# aw_801_oscilloscope.net
KiCad netlist of a schematic drawn in EAGLE
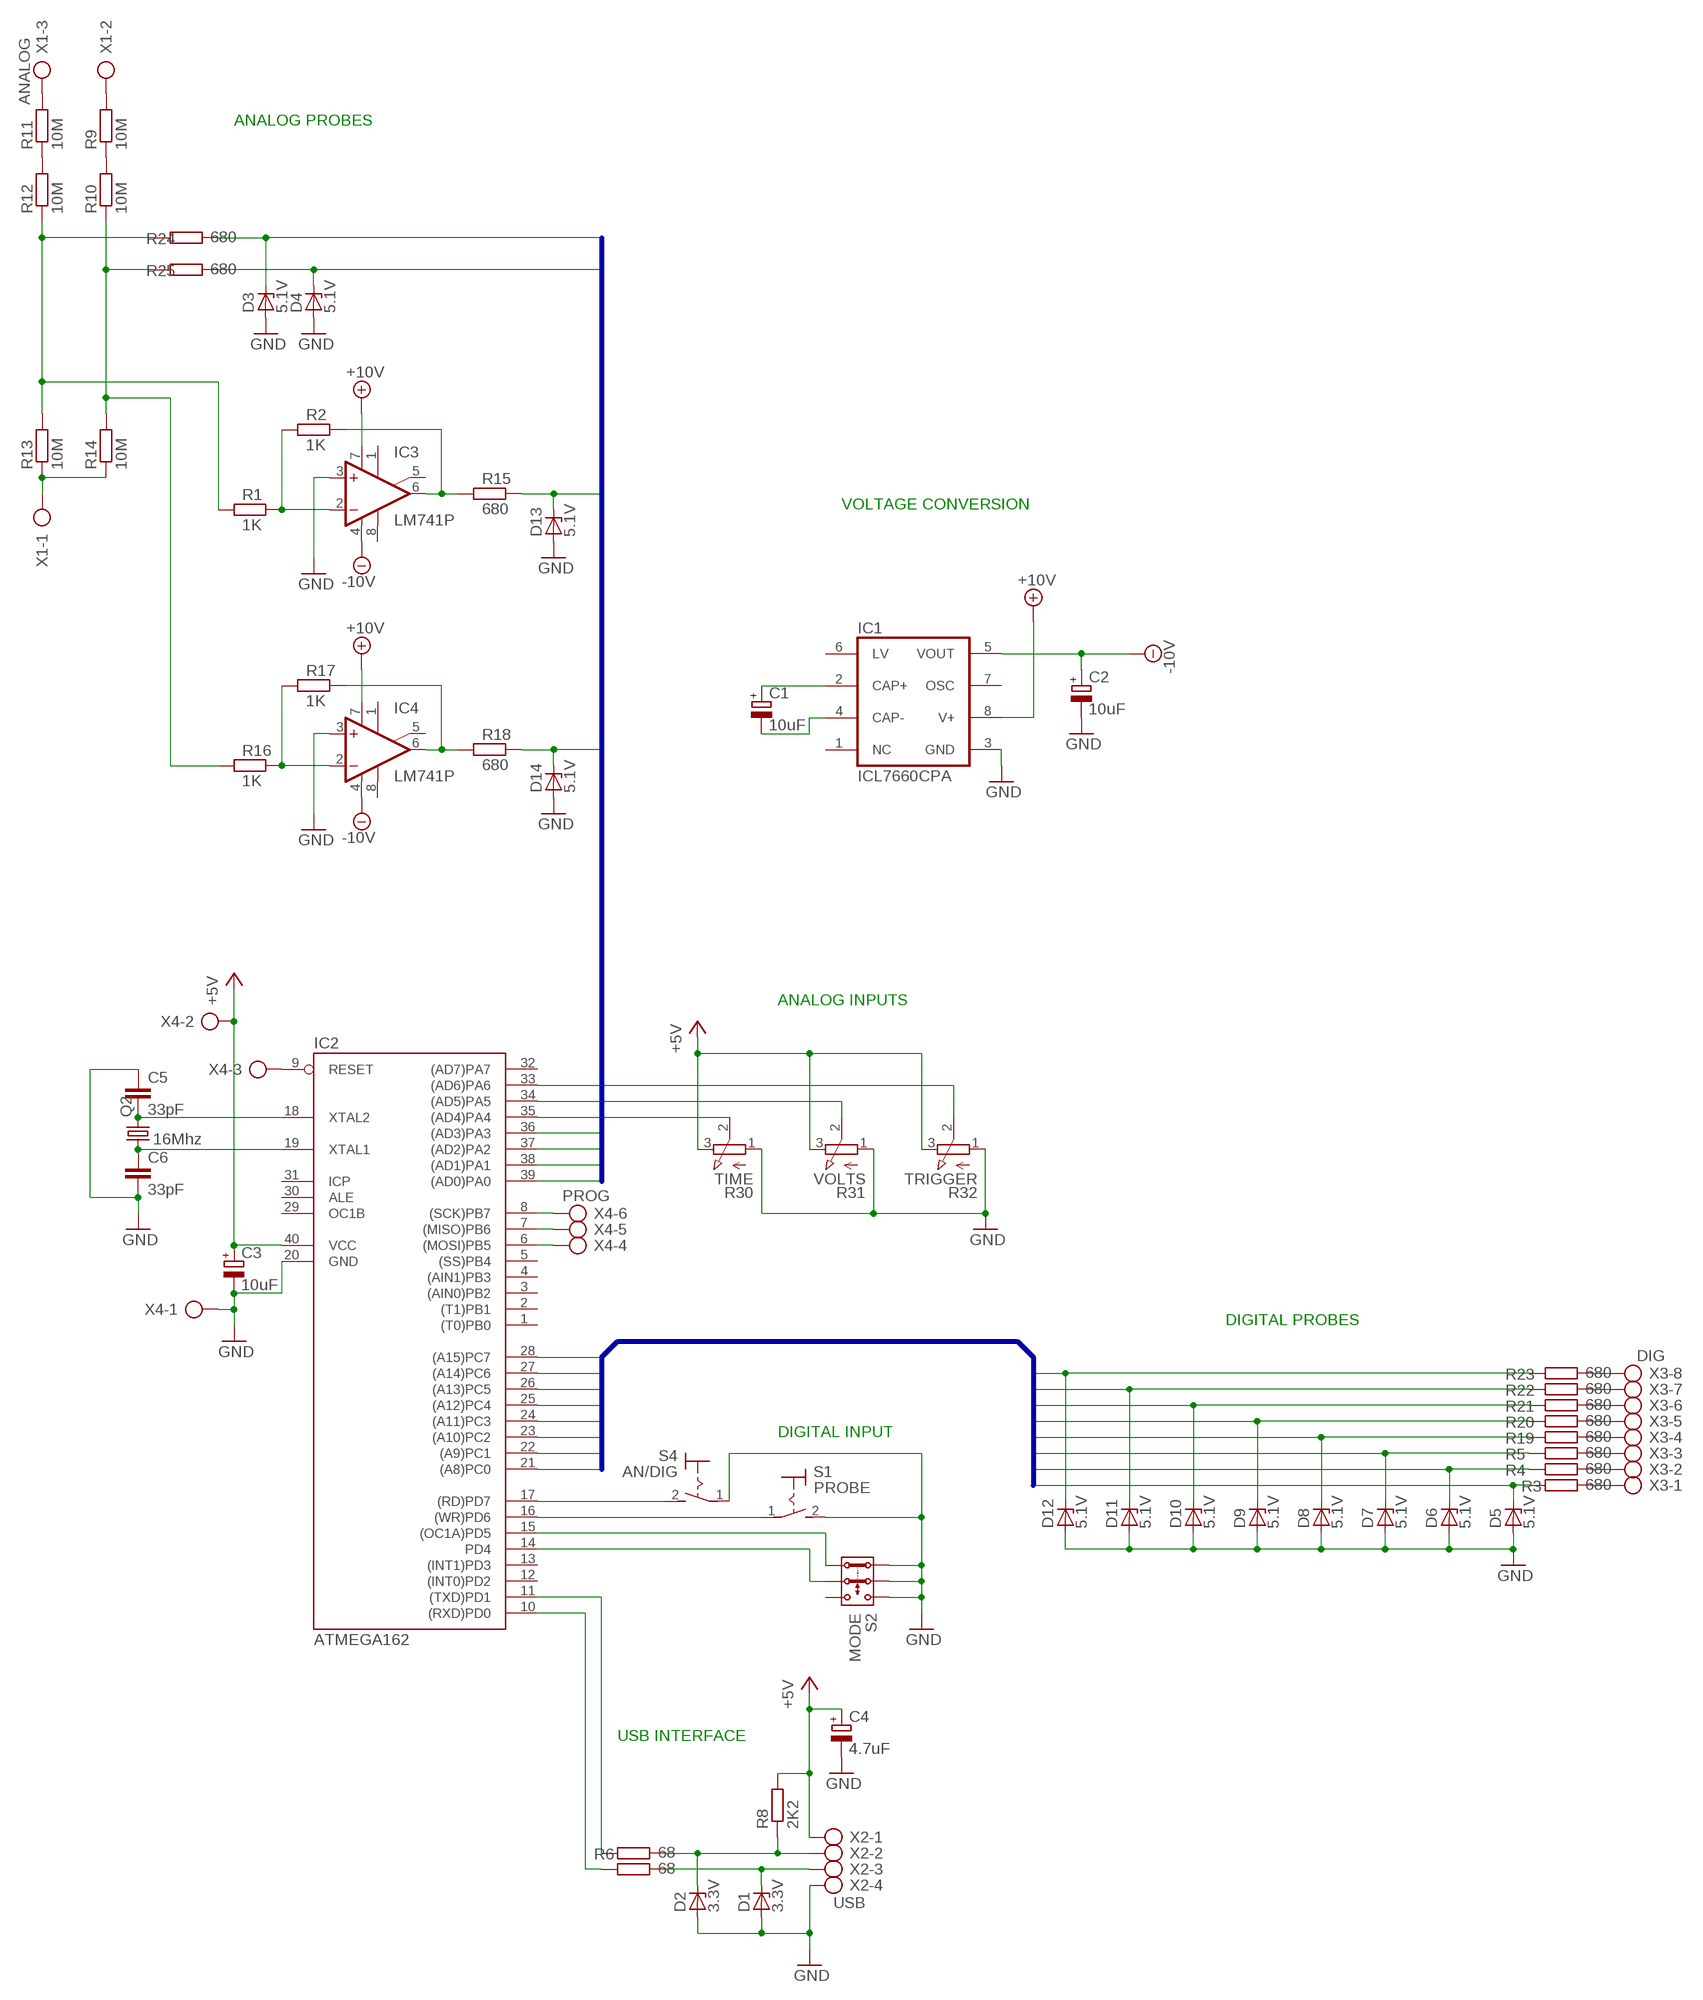
[diagram p0: schematic, sheet 1]

(export (version "E")
  (design (tool "Eeschema 10.0.6"))
  (components
    (comp (ref "C1")
      (value "10uF")
      (footprint "eagle-import:E2,5-6")
      (libsource (lib "eagle-import") (part "CPOL-EUE2.5-6"))
    )
    (comp (ref "C2")
      (value "10uF")
      (footprint "eagle-import:E2,5-6")
      (libsource (lib "eagle-import") (part "CPOL-EUE2.5-6"))
    )
    (comp (ref "C3")
      (value "10uF")
      (footprint "eagle-import:E2,5-6")
      (libsource (lib "eagle-import") (part "CPOL-EUE2.5-6"))
    )
    (comp (ref "C4")
      (value "4.7uF")
      (footprint "eagle-import:E2,5-6")
      (libsource (lib "eagle-import") (part "CPOL-EUE2.5-6"))
    )
    (comp (ref "C5")
      (value "33pF")
      (footprint "eagle-import:C050-030X075")
      (libsource (lib "eagle-import") (part "C-EU050-030X075"))
    )
    (comp (ref "C6")
      (value "33pF")
      (footprint "eagle-import:C050-030X075")
      (libsource (lib "eagle-import") (part "C-EU050-030X075"))
    )
    (comp (ref "D1")
      (value "3.3V")
      (footprint "eagle-import:DO35Z10")
      (libsource (lib "eagle-import") (part "ZENER-DIODEDO35Z10"))
    )
    (comp (ref "D2")
      (value "3.3V")
      (footprint "eagle-import:DO35Z10")
      (libsource (lib "eagle-import") (part "ZENER-DIODEDO35Z10"))
    )
    (comp (ref "D3")
      (value "5.1V")
      (footprint "eagle-import:DO35Z10")
      (libsource (lib "eagle-import") (part "ZENER-DIODEDO35Z10"))
    )
    (comp (ref "D4")
      (value "5.1V")
      (footprint "eagle-import:DO35Z10")
      (libsource (lib "eagle-import") (part "ZENER-DIODEDO35Z10"))
    )
    (comp (ref "D5")
      (value "5.1V")
      (footprint "eagle-import:DO35Z10")
      (libsource (lib "eagle-import") (part "ZENER-DIODEDO35Z10"))
    )
    (comp (ref "D6")
      (value "5.1V")
      (footprint "eagle-import:DO35Z10")
      (libsource (lib "eagle-import") (part "ZENER-DIODEDO35Z10"))
    )
    (comp (ref "D7")
      (value "5.1V")
      (footprint "eagle-import:DO35Z10")
      (libsource (lib "eagle-import") (part "ZENER-DIODEDO35Z10"))
    )
    (comp (ref "D8")
      (value "5.1V")
      (footprint "eagle-import:DO35Z10")
      (libsource (lib "eagle-import") (part "ZENER-DIODEDO35Z10"))
    )
    (comp (ref "D9")
      (value "5.1V")
      (footprint "eagle-import:DO35Z10")
      (libsource (lib "eagle-import") (part "ZENER-DIODEDO35Z10"))
    )
    (comp (ref "D10")
      (value "5.1V")
      (footprint "eagle-import:DO35Z10")
      (libsource (lib "eagle-import") (part "ZENER-DIODEDO35Z10"))
    )
    (comp (ref "D11")
      (value "5.1V")
      (footprint "eagle-import:DO35Z10")
      (libsource (lib "eagle-import") (part "ZENER-DIODEDO35Z10"))
    )
    (comp (ref "D12")
      (value "5.1V")
      (footprint "eagle-import:DO35Z10")
      (libsource (lib "eagle-import") (part "ZENER-DIODEDO35Z10"))
    )
    (comp (ref "D13")
      (value "5.1V")
      (footprint "eagle-import:DO35Z10")
      (libsource (lib "eagle-import") (part "ZENER-DIODEDO35Z10"))
    )
    (comp (ref "D14")
      (value "5.1V")
      (footprint "eagle-import:DO35Z10")
      (libsource (lib "eagle-import") (part "ZENER-DIODEDO35Z10"))
    )
    (comp (ref "IC1")
      (value "ICL7660CPA")
      (footprint "eagle-import:DIL08")
      (fields (field (name "MF") "INTERSIL"))
      (libsource (lib "eagle-import") (part "ICL7660CPA"))
    )
    (comp (ref "IC2")
      (value "ATMEGA162")
      (footprint "eagle-import:DIL40")
      (libsource (lib "eagle-import") (part "AT90S8515P"))
    )
    (comp (ref "IC3")
      (value "LM741P")
      (footprint "eagle-import:DIL08")
      (libsource (lib "eagle-import") (part "741PLM"))
    )
    (comp (ref "IC4")
      (value "LM741P")
      (footprint "eagle-import:DIL08")
      (libsource (lib "eagle-import") (part "741PLM"))
    )
    (comp (ref "Q2")
      (value "16Mhz")
      (footprint "eagle-import:HC49U70")
      (libsource (lib "eagle-import") (part "CRYSTALHC49U70"))
    )
    (comp (ref "R1")
      (value "1K")
      (footprint "eagle-import:0207_10")
      (libsource (lib "eagle-import") (part "R-EU_0207/10"))
    )
    (comp (ref "R2")
      (value "1K")
      (footprint "eagle-import:0207_10")
      (libsource (lib "eagle-import") (part "R-EU_0207/10"))
    )
    (comp (ref "R3")
      (value "680")
      (footprint "eagle-import:0207_10")
      (libsource (lib "eagle-import") (part "R-EU_0207/10"))
    )
    (comp (ref "R4")
      (value "680")
      (footprint "eagle-import:0207_10")
      (libsource (lib "eagle-import") (part "R-EU_0207/10"))
    )
    (comp (ref "R5")
      (value "680")
      (footprint "eagle-import:0207_10")
      (libsource (lib "eagle-import") (part "R-EU_0207/10"))
    )
    (comp (ref "R6")
      (value "68")
      (footprint "eagle-import:0207_10")
      (libsource (lib "eagle-import") (part "R-EU_0207/10"))
    )
    (comp (ref "R7")
      (value "68")
      (footprint "eagle-import:0207_10")
      (libsource (lib "eagle-import") (part "R-EU_0207/10"))
    )
    (comp (ref "R8")
      (value "2K2")
      (footprint "eagle-import:0207_10")
      (libsource (lib "eagle-import") (part "R-EU_0207/10"))
    )
    (comp (ref "R9")
      (value "10M")
      (footprint "eagle-import:0207_10")
      (libsource (lib "eagle-import") (part "R-EU_0207/10"))
    )
    (comp (ref "R10")
      (value "10M")
      (footprint "eagle-import:0207_10")
      (libsource (lib "eagle-import") (part "R-EU_0207/10"))
    )
    (comp (ref "R11")
      (value "10M")
      (footprint "eagle-import:0207_10")
      (libsource (lib "eagle-import") (part "R-EU_0207/10"))
    )
    (comp (ref "R12")
      (value "10M")
      (footprint "eagle-import:0207_10")
      (libsource (lib "eagle-import") (part "R-EU_0207/10"))
    )
    (comp (ref "R13")
      (value "10M")
      (footprint "eagle-import:0207_10")
      (libsource (lib "eagle-import") (part "R-EU_0207/10"))
    )
    (comp (ref "R14")
      (value "10M")
      (footprint "eagle-import:0207_10")
      (libsource (lib "eagle-import") (part "R-EU_0207/10"))
    )
    (comp (ref "R15")
      (value "680")
      (footprint "eagle-import:0207_10")
      (libsource (lib "eagle-import") (part "R-EU_0207/10"))
    )
    (comp (ref "R16")
      (value "1K")
      (footprint "eagle-import:0207_10")
      (libsource (lib "eagle-import") (part "R-EU_0207/10"))
    )
    (comp (ref "R17")
      (value "1K")
      (footprint "eagle-import:0207_10")
      (libsource (lib "eagle-import") (part "R-EU_0207/10"))
    )
    (comp (ref "R18")
      (value "680")
      (footprint "eagle-import:0207_10")
      (libsource (lib "eagle-import") (part "R-EU_0207/10"))
    )
    (comp (ref "R19")
      (value "680")
      (footprint "eagle-import:0207_10")
      (libsource (lib "eagle-import") (part "R-EU_0207/10"))
    )
    (comp (ref "R20")
      (value "680")
      (footprint "eagle-import:0207_10")
      (libsource (lib "eagle-import") (part "R-EU_0207/10"))
    )
    (comp (ref "R21")
      (value "680")
      (footprint "eagle-import:0207_10")
      (libsource (lib "eagle-import") (part "R-EU_0207/10"))
    )
    (comp (ref "R22")
      (value "680")
      (footprint "eagle-import:0207_10")
      (libsource (lib "eagle-import") (part "R-EU_0207/10"))
    )
    (comp (ref "R23")
      (value "680")
      (footprint "eagle-import:0207_10")
      (libsource (lib "eagle-import") (part "R-EU_0207/10"))
    )
    (comp (ref "R24")
      (value "680")
      (footprint "eagle-import:0207_10")
      (libsource (lib "eagle-import") (part "R-EU_0207/10"))
    )
    (comp (ref "R25")
      (value "680")
      (footprint "eagle-import:0207_10")
      (libsource (lib "eagle-import") (part "R-EU_0207/10"))
    )
    (comp (ref "R30")
      (value "TIME")
      (footprint "eagle-import:3RP_1610N")
      (libsource (lib "eagle-import") (part "3RP/1610N"))
    )
    (comp (ref "R31")
      (value "VOLTS")
      (footprint "eagle-import:3RP_1610N")
      (libsource (lib "eagle-import") (part "3RP/1610N"))
    )
    (comp (ref "R32")
      (value "TRIGGER")
      (footprint "eagle-import:3RP_1610N")
      (libsource (lib "eagle-import") (part "3RP/1610N"))
    )
    (comp (ref "S1")
      (value "PROBE")
      (footprint "eagle-import:MS243")
      (libsource (lib "eagle-import") (part "MS243"))
    )
    (comp (ref "S2")
      (value "MODE")
      (footprint "eagle-import:2P2T")
      (libsource (lib "eagle-import") (part "2P2T"))
    )
    (comp (ref "S4")
      (value "AN/DIG")
      (footprint "eagle-import:MS243")
      (libsource (lib "eagle-import") (part "MS243"))
    )
    (comp (ref "X1")
      (value "ANALOG")
      (footprint "eagle-import:AK500_3")
      (libsource (lib "eagle-import") (part "AK500/3"))
    )
    (comp (ref "X2")
      (value "USB")
      (footprint "eagle-import:AK500_4")
      (libsource (lib "eagle-import") (part "AK500/4"))
    )
    (comp (ref "X3")
      (value "DIG")
      (footprint "eagle-import:AK500_8")
      (libsource (lib "eagle-import") (part "AK500/8"))
    )
    (comp (ref "X4")
      (value "PROG")
      (footprint "eagle-import:AK300_6")
      (libsource (lib "eagle-import") (part "AK300/6"))
    )
  )
  (nets
    (net (code "1") (name "+5V") (class "Default")
      (node (ref "C3") (pin "+") (pinfunction "+_+") (pintype "passive"))
      (node (ref "C4") (pin "+") (pinfunction "+_+") (pintype "passive"))
      (node (ref "IC2") (pin "40") (pinfunction "VCC_40") (pintype "power_in"))
      (node (ref "R30") (pin "3") (pinfunction "E_3") (pintype "passive"))
      (node (ref "R31") (pin "3") (pinfunction "E_3") (pintype "passive"))
      (node (ref "R32") (pin "3") (pinfunction "E_3") (pintype "passive"))
      (node (ref "R8") (pin "2") (pinfunction "2_2") (pintype "passive"))
      (node (ref "X2") (pin "1") (pinfunction "KL_1") (pintype "passive"))
      (node (ref "X4") (pin "2") (pinfunction "KL_2") (pintype "passive"))
    )
    (net (code "2") (name "+10V") (class "Default")
      (node (ref "IC1") (pin "8") (pinfunction "V+_8") (pintype "power_in"))
      (node (ref "IC3") (pin "7") (pinfunction "V+_7") (pintype "power_in"))
      (node (ref "IC4") (pin "7") (pinfunction "V+_7") (pintype "power_in"))
    )
    (net (code "3") (name "-10V") (class "Default")
      (node (ref "C2") (pin "+") (pinfunction "+_+") (pintype "passive"))
      (node (ref "IC1") (pin "5") (pinfunction "VOUT_5") (pintype "power_in"))
      (node (ref "IC3") (pin "4") (pinfunction "V-_4") (pintype "power_in"))
      (node (ref "IC4") (pin "4") (pinfunction "V-_4") (pintype "power_in"))
    )
    (net (code "4") (name "/ANALOG0") (class "Default")
      (node (ref "D3") (pin "C") (pinfunction "C_C") (pintype "passive"))
      (node (ref "IC2") (pin "39") (pinfunction "(AD0)PA0_39") (pintype "bidirectional"))
      (node (ref "R24") (pin "2") (pinfunction "2_2") (pintype "passive"))
    )
    (net (code "5") (name "/ANALOG1") (class "Default")
      (node (ref "D4") (pin "C") (pinfunction "C_C") (pintype "passive"))
      (node (ref "IC2") (pin "38") (pinfunction "(AD1)PA1_38") (pintype "bidirectional"))
      (node (ref "R25") (pin "2") (pinfunction "2_2") (pintype "passive"))
    )
    (net (code "6") (name "/ANALOG2") (class "Default")
      (node (ref "D13") (pin "C") (pinfunction "C_C") (pintype "passive"))
      (node (ref "IC2") (pin "37") (pinfunction "(AD2)PA2_37") (pintype "bidirectional"))
      (node (ref "R15") (pin "2") (pinfunction "2_2") (pintype "passive"))
    )
    (net (code "7") (name "/ANALOG3") (class "Default")
      (node (ref "D14") (pin "C") (pinfunction "C_C") (pintype "passive"))
      (node (ref "IC2") (pin "36") (pinfunction "(AD3)PA3_36") (pintype "bidirectional"))
      (node (ref "R18") (pin "2") (pinfunction "2_2") (pintype "passive"))
    )
    (net (code "8") (name "/DIG0") (class "Default")
      (node (ref "D12") (pin "C") (pinfunction "C_C") (pintype "passive"))
      (node (ref "IC2") (pin "21") (pinfunction "(A8)PC0_21") (pintype "bidirectional"))
      (node (ref "R23") (pin "1") (pinfunction "1_1") (pintype "passive"))
    )
    (net (code "9") (name "/DIG1") (class "Default")
      (node (ref "D11") (pin "C") (pinfunction "C_C") (pintype "passive"))
      (node (ref "IC2") (pin "22") (pinfunction "(A9)PC1_22") (pintype "bidirectional"))
      (node (ref "R22") (pin "1") (pinfunction "1_1") (pintype "passive"))
    )
    (net (code "10") (name "/DIG2") (class "Default")
      (node (ref "D10") (pin "C") (pinfunction "C_C") (pintype "passive"))
      (node (ref "IC2") (pin "23") (pinfunction "(A10)PC2_23") (pintype "bidirectional"))
      (node (ref "R21") (pin "1") (pinfunction "1_1") (pintype "passive"))
    )
    (net (code "11") (name "/DIG3") (class "Default")
      (node (ref "D9") (pin "C") (pinfunction "C_C") (pintype "passive"))
      (node (ref "IC2") (pin "24") (pinfunction "(A11)PC3_24") (pintype "bidirectional"))
      (node (ref "R20") (pin "1") (pinfunction "1_1") (pintype "passive"))
    )
    (net (code "12") (name "/DIG4") (class "Default")
      (node (ref "D8") (pin "C") (pinfunction "C_C") (pintype "passive"))
      (node (ref "IC2") (pin "25") (pinfunction "(A12)PC4_25") (pintype "bidirectional"))
      (node (ref "R19") (pin "1") (pinfunction "1_1") (pintype "passive"))
    )
    (net (code "13") (name "/DIG5") (class "Default")
      (node (ref "D7") (pin "C") (pinfunction "C_C") (pintype "passive"))
      (node (ref "IC2") (pin "26") (pinfunction "(A13)PC5_26") (pintype "bidirectional"))
      (node (ref "R5") (pin "1") (pinfunction "1_1") (pintype "passive"))
    )
    (net (code "14") (name "/DIG6") (class "Default")
      (node (ref "D6") (pin "C") (pinfunction "C_C") (pintype "passive"))
      (node (ref "IC2") (pin "27") (pinfunction "(A14)PC6_27") (pintype "bidirectional"))
      (node (ref "R4") (pin "1") (pinfunction "1_1") (pintype "passive"))
    )
    (net (code "15") (name "/DIG7") (class "Default")
      (node (ref "D5") (pin "C") (pinfunction "C_C") (pintype "passive"))
      (node (ref "IC2") (pin "28") (pinfunction "(A15)PC7_28") (pintype "bidirectional"))
      (node (ref "R3") (pin "1") (pinfunction "1_1") (pintype "passive"))
    )
    (net (code "16") (name "GND") (class "Default")
      (node (ref "C2") (pin "-") (pinfunction "-_-") (pintype "passive"))
      (node (ref "C3") (pin "-") (pinfunction "-_-") (pintype "passive"))
      (node (ref "C4") (pin "-") (pinfunction "-_-") (pintype "passive"))
      (node (ref "C5") (pin "1") (pinfunction "1_1") (pintype "passive"))
      (node (ref "C6") (pin "2") (pinfunction "2_2") (pintype "passive"))
      (node (ref "D1") (pin "A") (pinfunction "A_A") (pintype "passive"))
      (node (ref "D10") (pin "A") (pinfunction "A_A") (pintype "passive"))
      (node (ref "D11") (pin "A") (pinfunction "A_A") (pintype "passive"))
      (node (ref "D12") (pin "A") (pinfunction "A_A") (pintype "passive"))
      (node (ref "D13") (pin "A") (pinfunction "A_A") (pintype "passive"))
      (node (ref "D14") (pin "A") (pinfunction "A_A") (pintype "passive"))
      (node (ref "D2") (pin "A") (pinfunction "A_A") (pintype "passive"))
      (node (ref "D3") (pin "A") (pinfunction "A_A") (pintype "passive"))
      (node (ref "D4") (pin "A") (pinfunction "A_A") (pintype "passive"))
      (node (ref "D5") (pin "A") (pinfunction "A_A") (pintype "passive"))
      (node (ref "D6") (pin "A") (pinfunction "A_A") (pintype "passive"))
      (node (ref "D7") (pin "A") (pinfunction "A_A") (pintype "passive"))
      (node (ref "D8") (pin "A") (pinfunction "A_A") (pintype "passive"))
      (node (ref "D9") (pin "A") (pinfunction "A_A") (pintype "passive"))
      (node (ref "IC1") (pin "3") (pinfunction "GND_3") (pintype "power_in"))
      (node (ref "IC2") (pin "20") (pinfunction "GND_20") (pintype "power_in"))
      (node (ref "IC3") (pin "3") (pinfunction "+IN_3") (pintype "input"))
      (node (ref "IC4") (pin "3") (pinfunction "+IN_3") (pintype "input"))
      (node (ref "R30") (pin "1") (pinfunction "A_1") (pintype "passive"))
      (node (ref "R31") (pin "1") (pinfunction "A_1") (pintype "passive"))
      (node (ref "R32") (pin "1") (pinfunction "A_1") (pintype "passive"))
      (node (ref "S1") (pin "2") (pinfunction "S_2") (pintype "passive"))
      (node (ref "S2") (pin "1.1") (pinfunction "1.1_1.1") (pintype "passive"))
      (node (ref "S2") (pin "2.1") (pinfunction "2.1_2.1") (pintype "passive"))
      (node (ref "S2") (pin "3.1") (pinfunction "3.1_3.1") (pintype "passive"))
      (node (ref "S4") (pin "1") (pinfunction "P_1") (pintype "passive"))
      (node (ref "X2") (pin "4") (pinfunction "KL_4") (pintype "passive"))
      (node (ref "X4") (pin "1") (pinfunction "KL_1") (pintype "passive"))
    )
    (net (code "17") (name "Net-(IC1-CAP+)") (class "Default")
      (node (ref "C1") (pin "+") (pinfunction "+_+") (pintype "passive"))
      (node (ref "IC1") (pin "2") (pinfunction "CAP+_2") (pintype "passive"))
    )
    (net (code "18") (name "Net-(IC1-CAP-)") (class "Default")
      (node (ref "C1") (pin "-") (pinfunction "-_-") (pintype "passive"))
      (node (ref "IC1") (pin "4") (pinfunction "CAP-_4") (pintype "passive"))
    )
    (net (code "19") (name "Net-(IC2-(AD4)PA4)") (class "Default")
      (node (ref "IC2") (pin "35") (pinfunction "(AD4)PA4_35") (pintype "bidirectional"))
      (node (ref "R30") (pin "2") (pinfunction "S_2") (pintype "passive"))
    )
    (net (code "20") (name "Net-(IC2-(AD5)PA5)") (class "Default")
      (node (ref "IC2") (pin "34") (pinfunction "(AD5)PA5_34") (pintype "bidirectional"))
      (node (ref "R31") (pin "2") (pinfunction "S_2") (pintype "passive"))
    )
    (net (code "21") (name "Net-(IC2-(AD6)PA6)") (class "Default")
      (node (ref "IC2") (pin "33") (pinfunction "(AD6)PA6_33") (pintype "bidirectional"))
      (node (ref "R32") (pin "2") (pinfunction "S_2") (pintype "passive"))
    )
    (net (code "22") (name "Net-(IC2-(MISO)PB6)") (class "Default")
      (node (ref "IC2") (pin "7") (pinfunction "(MISO)PB6_7") (pintype "bidirectional"))
      (node (ref "X4") (pin "5") (pinfunction "KL_5") (pintype "passive"))
    )
    (net (code "23") (name "Net-(IC2-(MOSI)PB5)") (class "Default")
      (node (ref "IC2") (pin "6") (pinfunction "(MOSI)PB5_6") (pintype "bidirectional"))
      (node (ref "X4") (pin "4") (pinfunction "KL_4") (pintype "passive"))
    )
    (net (code "24") (name "Net-(IC2-(OC1A)PD5)") (class "Default")
      (node (ref "IC2") (pin "15") (pinfunction "(OC1A)PD5_15") (pintype "bidirectional"))
      (node (ref "S2") (pin "1.2") (pinfunction "1.2_1.2") (pintype "passive"))
    )
    (net (code "25") (name "Net-(IC2-(RD)PD7)") (class "Default")
      (node (ref "IC2") (pin "17") (pinfunction "(RD)PD7_17") (pintype "bidirectional"))
      (node (ref "S4") (pin "2") (pinfunction "S_2") (pintype "passive"))
    )
    (net (code "26") (name "Net-(IC2-(RXD)PD0)") (class "Default")
      (node (ref "IC2") (pin "10") (pinfunction "(RXD)PD0_10") (pintype "bidirectional"))
      (node (ref "R7") (pin "1") (pinfunction "1_1") (pintype "passive"))
    )
    (net (code "27") (name "Net-(IC2-(SCK)PB7)") (class "Default")
      (node (ref "IC2") (pin "8") (pinfunction "(SCK)PB7_8") (pintype "bidirectional"))
      (node (ref "X4") (pin "6") (pinfunction "KL_6") (pintype "passive"))
    )
    (net (code "28") (name "Net-(IC2-(TXD)PD1)") (class "Default")
      (node (ref "IC2") (pin "11") (pinfunction "(TXD)PD1_11") (pintype "bidirectional"))
      (node (ref "R6") (pin "1") (pinfunction "1_1") (pintype "passive"))
    )
    (net (code "29") (name "Net-(IC2-(WR)PD6)") (class "Default")
      (node (ref "IC2") (pin "16") (pinfunction "(WR)PD6_16") (pintype "bidirectional"))
      (node (ref "S1") (pin "1") (pinfunction "P_1") (pintype "passive"))
    )
    (net (code "30") (name "Net-(IC2-PD4)") (class "Default")
      (node (ref "IC2") (pin "14") (pinfunction "PD4_14") (pintype "bidirectional"))
      (node (ref "S2") (pin "2.2") (pinfunction "2.2_2.2") (pintype "passive"))
    )
    (net (code "31") (name "Net-(IC2-RESET)") (class "Default")
      (node (ref "IC2") (pin "9") (pinfunction "RESET_9") (pintype "input"))
      (node (ref "X4") (pin "3") (pinfunction "KL_3") (pintype "passive"))
    )
    (net (code "32") (name "Net-(IC2-XTAL1)") (class "Default")
      (node (ref "C6") (pin "1") (pinfunction "1_1") (pintype "passive"))
      (node (ref "IC2") (pin "19") (pinfunction "XTAL1_19") (pintype "bidirectional"))
      (node (ref "Q2") (pin "1") (pinfunction "1_1") (pintype "passive"))
    )
    (net (code "33") (name "Net-(IC2-XTAL2)") (class "Default")
      (node (ref "C5") (pin "2") (pinfunction "2_2") (pintype "passive"))
      (node (ref "IC2") (pin "18") (pinfunction "XTAL2_18") (pintype "bidirectional"))
      (node (ref "Q2") (pin "2") (pinfunction "2_2") (pintype "passive"))
    )
    (net (code "34") (name "Net-(IC3--IN)") (class "Default")
      (node (ref "IC3") (pin "2") (pinfunction "-IN_2") (pintype "input"))
      (node (ref "R1") (pin "2") (pinfunction "2_2") (pintype "passive"))
      (node (ref "R2") (pin "1") (pinfunction "1_1") (pintype "passive"))
    )
    (net (code "35") (name "Net-(IC3-OUT)") (class "Default")
      (node (ref "IC3") (pin "6") (pinfunction "OUT_6") (pintype "output"))
      (node (ref "R15") (pin "1") (pinfunction "1_1") (pintype "passive"))
      (node (ref "R2") (pin "2") (pinfunction "2_2") (pintype "passive"))
    )
    (net (code "36") (name "Net-(IC4--IN)") (class "Default")
      (node (ref "IC4") (pin "2") (pinfunction "-IN_2") (pintype "input"))
      (node (ref "R16") (pin "2") (pinfunction "2_2") (pintype "passive"))
      (node (ref "R17") (pin "1") (pinfunction "1_1") (pintype "passive"))
    )
    (net (code "37") (name "Net-(IC4-OUT)") (class "Default")
      (node (ref "IC4") (pin "6") (pinfunction "OUT_6") (pintype "output"))
      (node (ref "R17") (pin "2") (pinfunction "2_2") (pintype "passive"))
      (node (ref "R18") (pin "1") (pinfunction "1_1") (pintype "passive"))
    )
    (net (code "38") (name "Net-(R1-Pad1)") (class "Default")
      (node (ref "R1") (pin "1") (pinfunction "1_1") (pintype "passive"))
      (node (ref "R12") (pin "1") (pinfunction "1_1") (pintype "passive"))
      (node (ref "R13") (pin "2") (pinfunction "2_2") (pintype "passive"))
      (node (ref "R24") (pin "1") (pinfunction "1_1") (pintype "passive"))
    )
    (net (code "39") (name "Net-(R10-Pad1)") (class "Default")
      (node (ref "R10") (pin "1") (pinfunction "1_1") (pintype "passive"))
      (node (ref "R14") (pin "2") (pinfunction "2_2") (pintype "passive"))
      (node (ref "R16") (pin "1") (pinfunction "1_1") (pintype "passive"))
      (node (ref "R25") (pin "1") (pinfunction "1_1") (pintype "passive"))
    )
    (net (code "40") (name "Net-(R10-Pad2)") (class "Default")
      (node (ref "R10") (pin "2") (pinfunction "2_2") (pintype "passive"))
      (node (ref "R9") (pin "1") (pinfunction "1_1") (pintype "passive"))
    )
    (net (code "41") (name "Net-(R11-Pad1)") (class "Default")
      (node (ref "R11") (pin "1") (pinfunction "1_1") (pintype "passive"))
      (node (ref "R12") (pin "2") (pinfunction "2_2") (pintype "passive"))
    )
    (net (code "42") (name "Net-(X1A-KL)") (class "Default")
      (node (ref "R13") (pin "1") (pinfunction "1_1") (pintype "passive"))
      (node (ref "R14") (pin "1") (pinfunction "1_1") (pintype "passive"))
      (node (ref "X1") (pin "1") (pinfunction "KL_1") (pintype "passive"))
    )
    (net (code "43") (name "Net-(X1B-KL)") (class "Default")
      (node (ref "R9") (pin "2") (pinfunction "2_2") (pintype "passive"))
      (node (ref "X1") (pin "2") (pinfunction "KL_2") (pintype "passive"))
    )
    (net (code "44") (name "Net-(X1C-KL)") (class "Default")
      (node (ref "R11") (pin "2") (pinfunction "2_2") (pintype "passive"))
      (node (ref "X1") (pin "3") (pinfunction "KL_3") (pintype "passive"))
    )
    (net (code "45") (name "Net-(X2B-KL)") (class "Default")
      (node (ref "D2") (pin "C") (pinfunction "C_C") (pintype "passive"))
      (node (ref "R6") (pin "2") (pinfunction "2_2") (pintype "passive"))
      (node (ref "R8") (pin "1") (pinfunction "1_1") (pintype "passive"))
      (node (ref "X2") (pin "2") (pinfunction "KL_2") (pintype "passive"))
    )
    (net (code "46") (name "Net-(X2C-KL)") (class "Default")
      (node (ref "D1") (pin "C") (pinfunction "C_C") (pintype "passive"))
      (node (ref "R7") (pin "2") (pinfunction "2_2") (pintype "passive"))
      (node (ref "X2") (pin "3") (pinfunction "KL_3") (pintype "passive"))
    )
    (net (code "47") (name "Net-(X3A-KL)") (class "Default")
      (node (ref "R3") (pin "2") (pinfunction "2_2") (pintype "passive"))
      (node (ref "X3") (pin "1") (pinfunction "KL_1") (pintype "passive"))
    )
    (net (code "48") (name "Net-(X3B-KL)") (class "Default")
      (node (ref "R4") (pin "2") (pinfunction "2_2") (pintype "passive"))
      (node (ref "X3") (pin "2") (pinfunction "KL_2") (pintype "passive"))
    )
    (net (code "49") (name "Net-(X3C-KL)") (class "Default")
      (node (ref "R5") (pin "2") (pinfunction "2_2") (pintype "passive"))
      (node (ref "X3") (pin "3") (pinfunction "KL_3") (pintype "passive"))
    )
    (net (code "50") (name "Net-(X3D-KL)") (class "Default")
      (node (ref "R19") (pin "2") (pinfunction "2_2") (pintype "passive"))
      (node (ref "X3") (pin "4") (pinfunction "KL_4") (pintype "passive"))
    )
    (net (code "51") (name "Net-(X3E-KL)") (class "Default")
      (node (ref "R20") (pin "2") (pinfunction "2_2") (pintype "passive"))
      (node (ref "X3") (pin "5") (pinfunction "KL_5") (pintype "passive"))
    )
    (net (code "52") (name "Net-(X3F-KL)") (class "Default")
      (node (ref "R21") (pin "2") (pinfunction "2_2") (pintype "passive"))
      (node (ref "X3") (pin "6") (pinfunction "KL_6") (pintype "passive"))
    )
    (net (code "53") (name "Net-(X3G-KL)") (class "Default")
      (node (ref "R22") (pin "2") (pinfunction "2_2") (pintype "passive"))
      (node (ref "X3") (pin "7") (pinfunction "KL_7") (pintype "passive"))
    )
    (net (code "54") (name "Net-(X3H-KL)") (class "Default")
      (node (ref "R23") (pin "2") (pinfunction "2_2") (pintype "passive"))
      (node (ref "X3") (pin "8") (pinfunction "KL_8") (pintype "passive"))
    )
    (net (code "55") (name "unconnected-(IC1-LV-Pad6)") (class "Default")
      (node (ref "IC1") (pin "6") (pinfunction "LV_6") (pintype "passive"))
    )
    (net (code "56") (name "unconnected-(IC1-NC-Pad1)") (class "Default")
      (node (ref "IC1") (pin "1") (pinfunction "NC_1") (pintype "no_connect"))
    )
    (net (code "57") (name "unconnected-(IC1-OSC-Pad7)") (class "Default")
      (node (ref "IC1") (pin "7") (pinfunction "OSC_7") (pintype "output"))
    )
    (net (code "58") (name "unconnected-(IC2-(AD7)PA7-Pad32)") (class "Default")
      (node (ref "IC2") (pin "32") (pinfunction "(AD7)PA7_32") (pintype "bidirectional"))
    )
    (net (code "59") (name "unconnected-(IC2-(AIN0)PB2-Pad3)") (class "Default")
      (node (ref "IC2") (pin "3") (pinfunction "(AIN0)PB2_3") (pintype "bidirectional"))
    )
    (net (code "60") (name "unconnected-(IC2-(AIN1)PB3-Pad4)") (class "Default")
      (node (ref "IC2") (pin "4") (pinfunction "(AIN1)PB3_4") (pintype "bidirectional"))
    )
    (net (code "61") (name "unconnected-(IC2-(INT0)PD2-Pad12)") (class "Default")
      (node (ref "IC2") (pin "12") (pinfunction "(INT0)PD2_12") (pintype "bidirectional"))
    )
    (net (code "62") (name "unconnected-(IC2-(INT1)PD3-Pad13)") (class "Default")
      (node (ref "IC2") (pin "13") (pinfunction "(INT1)PD3_13") (pintype "bidirectional"))
    )
    (net (code "63") (name "unconnected-(IC2-(SS)PB4-Pad5)") (class "Default")
      (node (ref "IC2") (pin "5") (pinfunction "(SS)PB4_5") (pintype "bidirectional"))
    )
    (net (code "64") (name "unconnected-(IC2-(T0)PB0-Pad1)") (class "Default")
      (node (ref "IC2") (pin "1") (pinfunction "(T0)PB0_1") (pintype "bidirectional"))
    )
    (net (code "65") (name "unconnected-(IC2-(T1)PB1-Pad2)") (class "Default")
      (node (ref "IC2") (pin "2") (pinfunction "(T1)PB1_2") (pintype "bidirectional"))
    )
    (net (code "66") (name "unconnected-(IC2-ALE-Pad30)") (class "Default")
      (node (ref "IC2") (pin "30") (pinfunction "ALE_30") (pintype "bidirectional"))
    )
    (net (code "67") (name "unconnected-(IC2-ICP-Pad31)") (class "Default")
      (node (ref "IC2") (pin "31") (pinfunction "ICP_31") (pintype "bidirectional"))
    )
    (net (code "68") (name "unconnected-(IC2-OC1B-Pad29)") (class "Default")
      (node (ref "IC2") (pin "29") (pinfunction "OC1B_29") (pintype "bidirectional"))
    )
    (net (code "69") (name "unconnected-(IC3-ON1-Pad1)") (class "Default")
      (node (ref "IC3") (pin "1") (pinfunction "ON1_1") (pintype "passive"))
    )
    (net (code "70") (name "unconnected-(IC3-ON2-Pad5)") (class "Default")
      (node (ref "IC3") (pin "5") (pinfunction "ON2_5") (pintype "passive"))
    )
    (net (code "71") (name "unconnected-(IC3-OPT-Pad8)") (class "Default")
      (node (ref "IC3") (pin "8") (pinfunction "OPT_8") (pintype "passive"))
    )
    (net (code "72") (name "unconnected-(IC4-ON1-Pad1)") (class "Default")
      (node (ref "IC4") (pin "1") (pinfunction "ON1_1") (pintype "passive"))
    )
    (net (code "73") (name "unconnected-(IC4-ON2-Pad5)") (class "Default")
      (node (ref "IC4") (pin "5") (pinfunction "ON2_5") (pintype "passive"))
    )
    (net (code "74") (name "unconnected-(IC4-OPT-Pad8)") (class "Default")
      (node (ref "IC4") (pin "8") (pinfunction "OPT_8") (pintype "passive"))
    )
    (net (code "75") (name "unconnected-(S2-Pad3.2)") (class "Default")
      (node (ref "S2") (pin "3.2") (pinfunction "3.2_3.2") (pintype "passive"))
    )
  )
)
